# rev_1_4.net
KiCad netlist of a schematic drawn in EAGLE
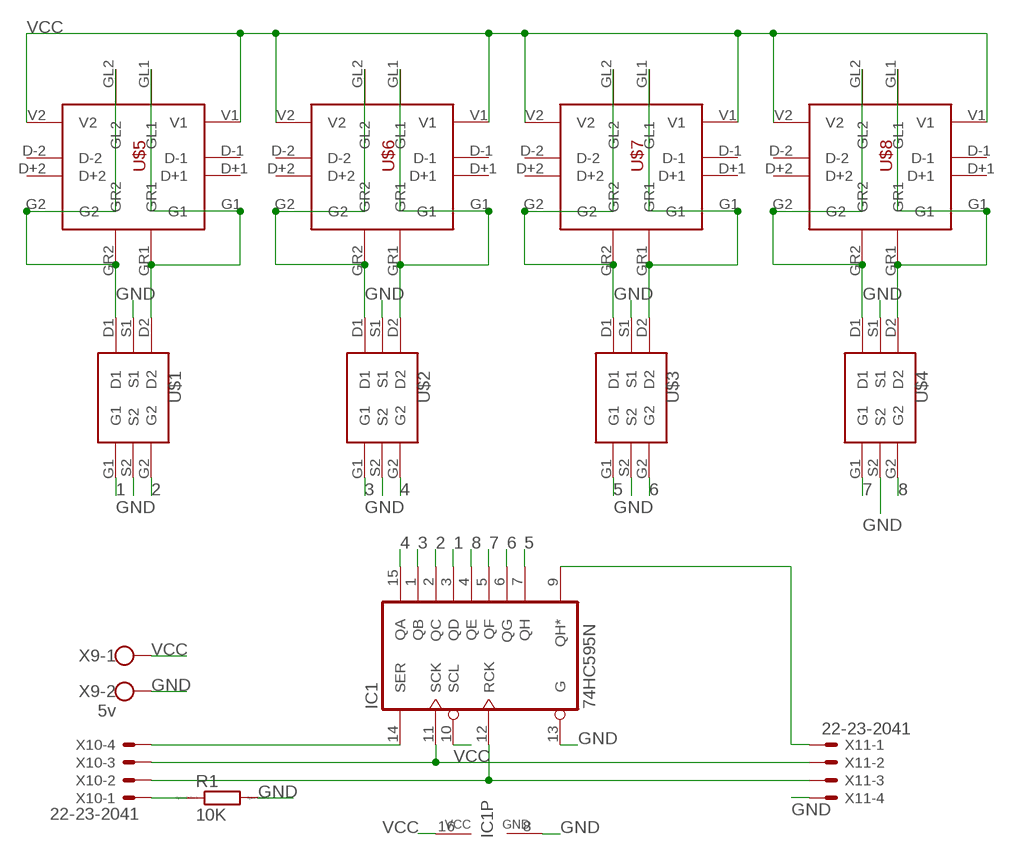
[diagram p0: schematic, sheet 1]

(export (version "E")
  (design (tool "Eeschema 10.0.6"))
  (components
    (comp (ref "IC1")
      (value "74HC595N")
      (footprint "eagle-import:DIL16")
      (libsource (lib "eagle-import") (part "74595NHC"))
    )
    (comp (ref "R1")
      (value "10K")
      (footprint "eagle-import:0204_7")
      (libsource (lib "eagle-import") (part "R0204/7"))
    )
    (comp (ref "U$1")
      (value "FDC6305N")
      (footprint "eagle-import:FDC6305")
      (libsource (lib "eagle-import") (part "FDC6305N"))
    )
    (comp (ref "U$2")
      (value "FDC6305N")
      (footprint "eagle-import:FDC6305")
      (libsource (lib "eagle-import") (part "FDC6305N"))
    )
    (comp (ref "U$3")
      (value "FDC6305N")
      (footprint "eagle-import:FDC6305")
      (libsource (lib "eagle-import") (part "FDC6305N"))
    )
    (comp (ref "U$4")
      (value "FDC6305N")
      (footprint "eagle-import:FDC6305")
      (libsource (lib "eagle-import") (part "FDC6305N"))
    )
    (comp (ref "U$5")
      (value "USB2V")
      (footprint "eagle-import:USB2V")
      (libsource (lib "eagle-import") (part "USB2V"))
    )
    (comp (ref "U$6")
      (value "USB2V")
      (footprint "eagle-import:USB2V")
      (libsource (lib "eagle-import") (part "USB2V"))
    )
    (comp (ref "U$7")
      (value "USB2V")
      (footprint "eagle-import:USB2V")
      (libsource (lib "eagle-import") (part "USB2V"))
    )
    (comp (ref "U$8")
      (value "USB2V")
      (footprint "eagle-import:USB2V")
      (libsource (lib "eagle-import") (part "USB2V"))
    )
    (comp (ref "X9")
      (value "5v")
      (footprint "eagle-import:W237-102")
      (fields (field (name "MPN") "237-102"))
      (libsource (lib "eagle-import") (part "W237-102"))
    )
    (comp (ref "X10")
      (value "22-23-2041")
      (footprint "eagle-import:22-23-2041")
      (fields (field (name "MF") "MOLEX"))
      (libsource (lib "eagle-import") (part "22-23-2041"))
    )
    (comp (ref "X11")
      (value "22-23-2041")
      (footprint "eagle-import:22-23-2041")
      (fields (field (name "MF") "MOLEX"))
      (libsource (lib "eagle-import") (part "22-23-2041"))
    )
  )
  (nets
    (net (code "1") (name "/1") (class "Default")
      (node (ref "IC1") (pin "3") (pinfunction "QD_3") (pintype "tri_state"))
      (node (ref "U$1") (pin "G1") (pinfunction "G1_G1") (pintype "bidirectional"))
    )
    (net (code "2") (name "/2") (class "Default")
      (node (ref "IC1") (pin "2") (pinfunction "QC_2") (pintype "tri_state"))
      (node (ref "U$1") (pin "G2") (pinfunction "G2_G2") (pintype "bidirectional"))
    )
    (net (code "3") (name "/3") (class "Default")
      (node (ref "IC1") (pin "1") (pinfunction "QB_1") (pintype "tri_state"))
      (node (ref "U$2") (pin "G1") (pinfunction "G1_G1") (pintype "bidirectional"))
    )
    (net (code "4") (name "/4") (class "Default")
      (node (ref "IC1") (pin "15") (pinfunction "QA_15") (pintype "tri_state"))
      (node (ref "U$2") (pin "G2") (pinfunction "G2_G2") (pintype "bidirectional"))
    )
    (net (code "5") (name "/5") (class "Default")
      (node (ref "IC1") (pin "7") (pinfunction "QH_7") (pintype "tri_state"))
      (node (ref "U$3") (pin "G1") (pinfunction "G1_G1") (pintype "bidirectional"))
    )
    (net (code "6") (name "/6") (class "Default")
      (node (ref "IC1") (pin "6") (pinfunction "QG_6") (pintype "tri_state"))
      (node (ref "U$3") (pin "G2") (pinfunction "G2_G2") (pintype "bidirectional"))
    )
    (net (code "7") (name "/7") (class "Default")
      (node (ref "IC1") (pin "5") (pinfunction "QF_5") (pintype "tri_state"))
      (node (ref "U$4") (pin "G1") (pinfunction "G1_G1") (pintype "bidirectional"))
    )
    (net (code "8") (name "/8") (class "Default")
      (node (ref "IC1") (pin "4") (pinfunction "QE_4") (pintype "tri_state"))
      (node (ref "U$4") (pin "G2") (pinfunction "G2_G2") (pintype "bidirectional"))
    )
    (net (code "9") (name "/GND") (class "Default")
      (node (ref "IC1") (pin "13") (pinfunction "G_13") (pintype "input"))
      (node (ref "IC1") (pin "8") (pinfunction "GND_8") (pintype "power_in"))
      (node (ref "R1") (pin "2") (pinfunction "2_2") (pintype "passive"))
      (node (ref "U$1") (pin "S1") (pinfunction "S1_S1") (pintype "bidirectional"))
      (node (ref "U$1") (pin "S2") (pinfunction "S2_S2") (pintype "bidirectional"))
      (node (ref "U$2") (pin "S1") (pinfunction "S1_S1") (pintype "bidirectional"))
      (node (ref "U$2") (pin "S2") (pinfunction "S2_S2") (pintype "bidirectional"))
      (node (ref "U$3") (pin "S1") (pinfunction "S1_S1") (pintype "bidirectional"))
      (node (ref "U$3") (pin "S2") (pinfunction "S2_S2") (pintype "bidirectional"))
      (node (ref "U$4") (pin "S1") (pinfunction "S1_S1") (pintype "bidirectional"))
      (node (ref "U$4") (pin "S2") (pinfunction "S2_S2") (pintype "bidirectional"))
      (node (ref "X11") (pin "4") (pinfunction "S_4") (pintype "passive"))
      (node (ref "X9") (pin "2") (pinfunction "KL_2") (pintype "passive"))
    )
    (net (code "10") (name "/VCC") (class "Default")
      (node (ref "IC1") (pin "10") (pinfunction "SCL_10") (pintype "input"))
      (node (ref "IC1") (pin "16") (pinfunction "VCC_16") (pintype "power_in"))
      (node (ref "U$5") (pin "V1") (pinfunction "V1_V1") (pintype "bidirectional"))
      (node (ref "U$5") (pin "V2") (pinfunction "V2_V2") (pintype "bidirectional"))
      (node (ref "U$6") (pin "V1") (pinfunction "V1_V1") (pintype "bidirectional"))
      (node (ref "U$6") (pin "V2") (pinfunction "V2_V2") (pintype "bidirectional"))
      (node (ref "U$7") (pin "V1") (pinfunction "V1_V1") (pintype "bidirectional"))
      (node (ref "U$7") (pin "V2") (pinfunction "V2_V2") (pintype "bidirectional"))
      (node (ref "U$8") (pin "V1") (pinfunction "V1_V1") (pintype "bidirectional"))
      (node (ref "U$8") (pin "V2") (pinfunction "V2_V2") (pintype "bidirectional"))
      (node (ref "X9") (pin "1") (pinfunction "KL_1") (pintype "passive"))
    )
    (net (code "11") (name "Net-(IC1A-QH*)") (class "Default")
      (node (ref "IC1") (pin "9") (pinfunction "QH*_9") (pintype "tri_state"))
      (node (ref "X11") (pin "1") (pinfunction "S_1") (pintype "passive"))
    )
    (net (code "12") (name "Net-(IC1A-RCK)") (class "Default")
      (node (ref "IC1") (pin "12") (pinfunction "RCK_12") (pintype "input"))
      (node (ref "X10") (pin "2") (pinfunction "S_2") (pintype "passive"))
      (node (ref "X11") (pin "3") (pinfunction "S_3") (pintype "passive"))
    )
    (net (code "13") (name "Net-(IC1A-SCK)") (class "Default")
      (node (ref "IC1") (pin "11") (pinfunction "SCK_11") (pintype "input"))
      (node (ref "X10") (pin "3") (pinfunction "S_3") (pintype "passive"))
      (node (ref "X11") (pin "2") (pinfunction "S_2") (pintype "passive"))
    )
    (net (code "14") (name "Net-(IC1A-SER)") (class "Default")
      (node (ref "IC1") (pin "14") (pinfunction "SER_14") (pintype "input"))
      (node (ref "X10") (pin "4") (pinfunction "S_4") (pintype "passive"))
    )
    (net (code "15") (name "Net-(U$1-PadD1)") (class "Default")
      (node (ref "U$1") (pin "D1") (pinfunction "D1_D1") (pintype "bidirectional"))
      (node (ref "U$5") (pin "G2") (pinfunction "G2_G2") (pintype "bidirectional"))
      (node (ref "U$5") (pin "GL2") (pinfunction "GL2_GL2") (pintype "bidirectional"))
      (node (ref "U$5") (pin "GR2") (pinfunction "GR2_GR2") (pintype "bidirectional"))
    )
    (net (code "16") (name "Net-(U$1-PadD2)") (class "Default")
      (node (ref "U$1") (pin "D2") (pinfunction "D2_D2") (pintype "bidirectional"))
      (node (ref "U$5") (pin "G1") (pinfunction "G1_G1") (pintype "bidirectional"))
      (node (ref "U$5") (pin "GL1") (pinfunction "GL1_GL1") (pintype "bidirectional"))
      (node (ref "U$5") (pin "GR1") (pinfunction "GR1_GR1") (pintype "bidirectional"))
    )
    (net (code "17") (name "Net-(U$2-PadD1)") (class "Default")
      (node (ref "U$2") (pin "D1") (pinfunction "D1_D1") (pintype "bidirectional"))
      (node (ref "U$6") (pin "G2") (pinfunction "G2_G2") (pintype "bidirectional"))
      (node (ref "U$6") (pin "GL2") (pinfunction "GL2_GL2") (pintype "bidirectional"))
      (node (ref "U$6") (pin "GR2") (pinfunction "GR2_GR2") (pintype "bidirectional"))
    )
    (net (code "18") (name "Net-(U$2-PadD2)") (class "Default")
      (node (ref "U$2") (pin "D2") (pinfunction "D2_D2") (pintype "bidirectional"))
      (node (ref "U$6") (pin "G1") (pinfunction "G1_G1") (pintype "bidirectional"))
      (node (ref "U$6") (pin "GL1") (pinfunction "GL1_GL1") (pintype "bidirectional"))
      (node (ref "U$6") (pin "GR1") (pinfunction "GR1_GR1") (pintype "bidirectional"))
    )
    (net (code "19") (name "Net-(U$3-PadD1)") (class "Default")
      (node (ref "U$3") (pin "D1") (pinfunction "D1_D1") (pintype "bidirectional"))
      (node (ref "U$7") (pin "G2") (pinfunction "G2_G2") (pintype "bidirectional"))
      (node (ref "U$7") (pin "GL2") (pinfunction "GL2_GL2") (pintype "bidirectional"))
      (node (ref "U$7") (pin "GR2") (pinfunction "GR2_GR2") (pintype "bidirectional"))
    )
    (net (code "20") (name "Net-(U$3-PadD2)") (class "Default")
      (node (ref "U$3") (pin "D2") (pinfunction "D2_D2") (pintype "bidirectional"))
      (node (ref "U$7") (pin "G1") (pinfunction "G1_G1") (pintype "bidirectional"))
      (node (ref "U$7") (pin "GL1") (pinfunction "GL1_GL1") (pintype "bidirectional"))
      (node (ref "U$7") (pin "GR1") (pinfunction "GR1_GR1") (pintype "bidirectional"))
    )
    (net (code "21") (name "Net-(U$4-PadD1)") (class "Default")
      (node (ref "U$4") (pin "D1") (pinfunction "D1_D1") (pintype "bidirectional"))
      (node (ref "U$8") (pin "G2") (pinfunction "G2_G2") (pintype "bidirectional"))
      (node (ref "U$8") (pin "GL2") (pinfunction "GL2_GL2") (pintype "bidirectional"))
      (node (ref "U$8") (pin "GR2") (pinfunction "GR2_GR2") (pintype "bidirectional"))
    )
    (net (code "22") (name "Net-(U$4-PadD2)") (class "Default")
      (node (ref "U$4") (pin "D2") (pinfunction "D2_D2") (pintype "bidirectional"))
      (node (ref "U$8") (pin "G1") (pinfunction "G1_G1") (pintype "bidirectional"))
      (node (ref "U$8") (pin "GL1") (pinfunction "GL1_GL1") (pintype "bidirectional"))
      (node (ref "U$8") (pin "GR1") (pinfunction "GR1_GR1") (pintype "bidirectional"))
    )
    (net (code "23") (name "Net-(X10A-S)") (class "Default")
      (node (ref "R1") (pin "1") (pinfunction "1_1") (pintype "passive"))
      (node (ref "X10") (pin "1") (pinfunction "S_1") (pintype "passive"))
    )
    (net (code "24") (name "unconnected-(U$5-PadD+1)") (class "Default")
      (node (ref "U$5") (pin "D+1") (pinfunction "D+1_D+1") (pintype "bidirectional"))
    )
    (net (code "25") (name "unconnected-(U$5-PadD+2)") (class "Default")
      (node (ref "U$5") (pin "D+2") (pinfunction "D+2_D+2") (pintype "bidirectional"))
    )
    (net (code "26") (name "unconnected-(U$5-PadD-1)") (class "Default")
      (node (ref "U$5") (pin "D-1") (pinfunction "D-1_D-1") (pintype "bidirectional"))
    )
    (net (code "27") (name "unconnected-(U$5-PadD-2)") (class "Default")
      (node (ref "U$5") (pin "D-2") (pinfunction "D-2_D-2") (pintype "bidirectional"))
    )
    (net (code "28") (name "unconnected-(U$6-PadD+1)") (class "Default")
      (node (ref "U$6") (pin "D+1") (pinfunction "D+1_D+1") (pintype "bidirectional"))
    )
    (net (code "29") (name "unconnected-(U$6-PadD+2)") (class "Default")
      (node (ref "U$6") (pin "D+2") (pinfunction "D+2_D+2") (pintype "bidirectional"))
    )
    (net (code "30") (name "unconnected-(U$6-PadD-1)") (class "Default")
      (node (ref "U$6") (pin "D-1") (pinfunction "D-1_D-1") (pintype "bidirectional"))
    )
    (net (code "31") (name "unconnected-(U$6-PadD-2)") (class "Default")
      (node (ref "U$6") (pin "D-2") (pinfunction "D-2_D-2") (pintype "bidirectional"))
    )
    (net (code "32") (name "unconnected-(U$7-PadD+1)") (class "Default")
      (node (ref "U$7") (pin "D+1") (pinfunction "D+1_D+1") (pintype "bidirectional"))
    )
    (net (code "33") (name "unconnected-(U$7-PadD+2)") (class "Default")
      (node (ref "U$7") (pin "D+2") (pinfunction "D+2_D+2") (pintype "bidirectional"))
    )
    (net (code "34") (name "unconnected-(U$7-PadD-1)") (class "Default")
      (node (ref "U$7") (pin "D-1") (pinfunction "D-1_D-1") (pintype "bidirectional"))
    )
    (net (code "35") (name "unconnected-(U$7-PadD-2)") (class "Default")
      (node (ref "U$7") (pin "D-2") (pinfunction "D-2_D-2") (pintype "bidirectional"))
    )
    (net (code "36") (name "unconnected-(U$8-PadD+1)") (class "Default")
      (node (ref "U$8") (pin "D+1") (pinfunction "D+1_D+1") (pintype "bidirectional"))
    )
    (net (code "37") (name "unconnected-(U$8-PadD+2)") (class "Default")
      (node (ref "U$8") (pin "D+2") (pinfunction "D+2_D+2") (pintype "bidirectional"))
    )
    (net (code "38") (name "unconnected-(U$8-PadD-1)") (class "Default")
      (node (ref "U$8") (pin "D-1") (pinfunction "D-1_D-1") (pintype "bidirectional"))
    )
    (net (code "39") (name "unconnected-(U$8-PadD-2)") (class "Default")
      (node (ref "U$8") (pin "D-2") (pinfunction "D-2_D-2") (pintype "bidirectional"))
    )
  )
)
